# DPT2_4.net
KiCad netlist of a schematic drawn in Altium Designer
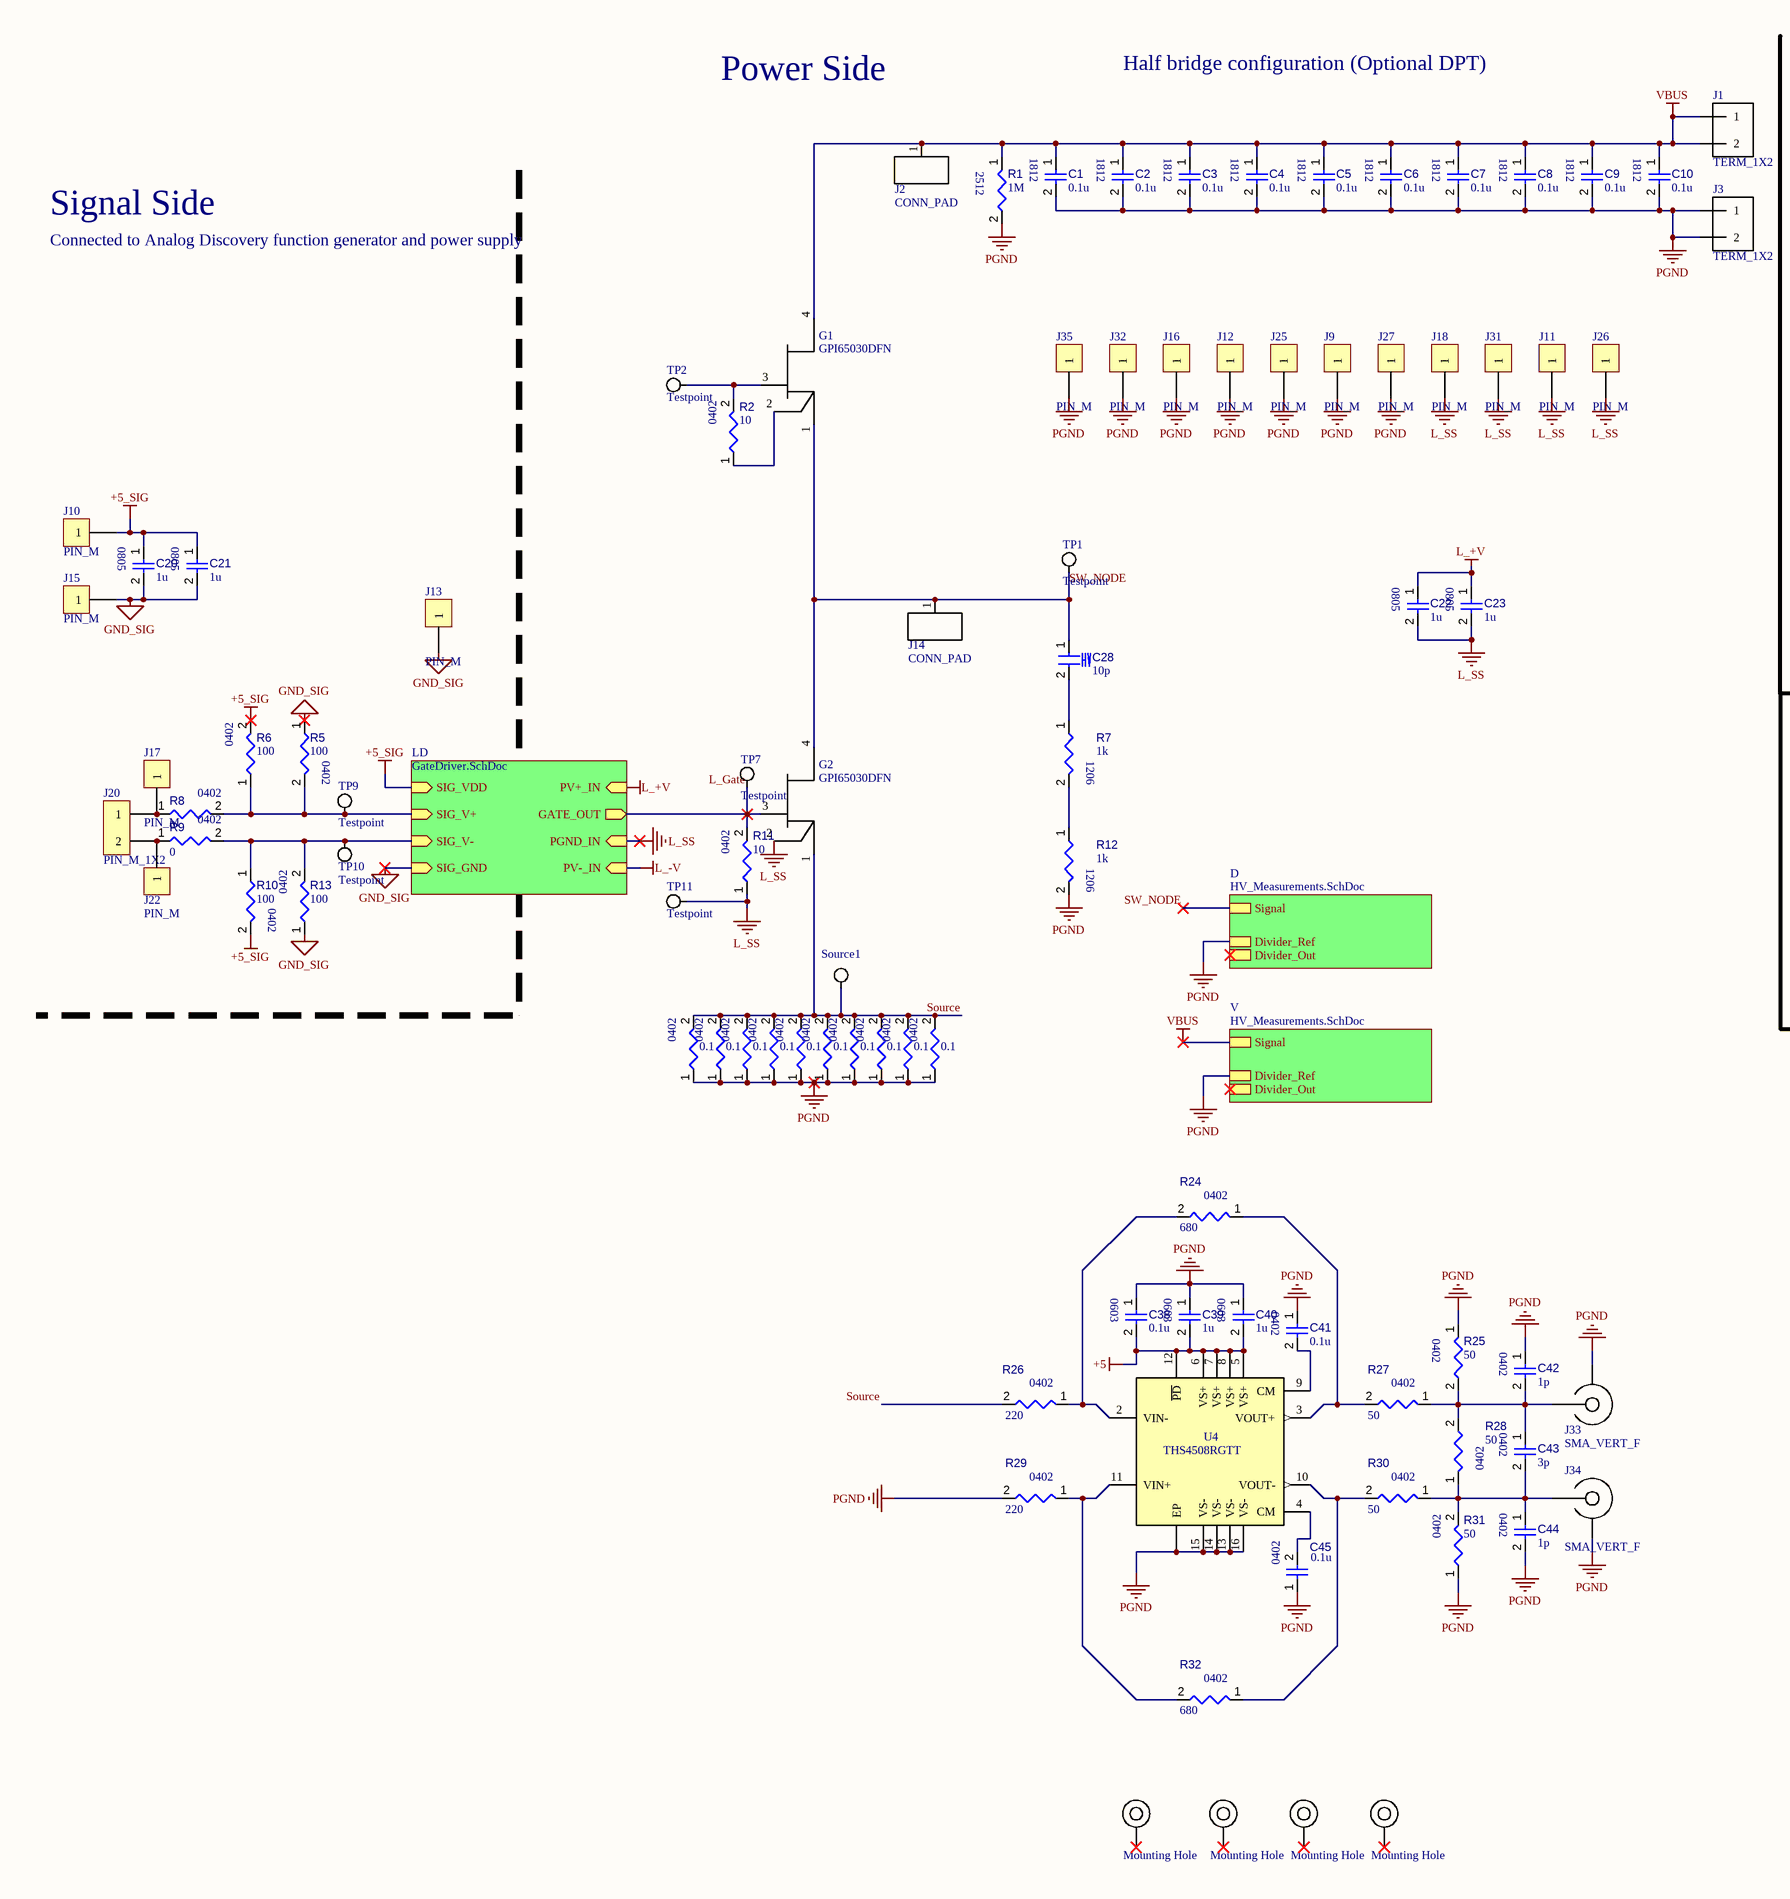
[diagram p0: DPT2.4.SchDoc, left]
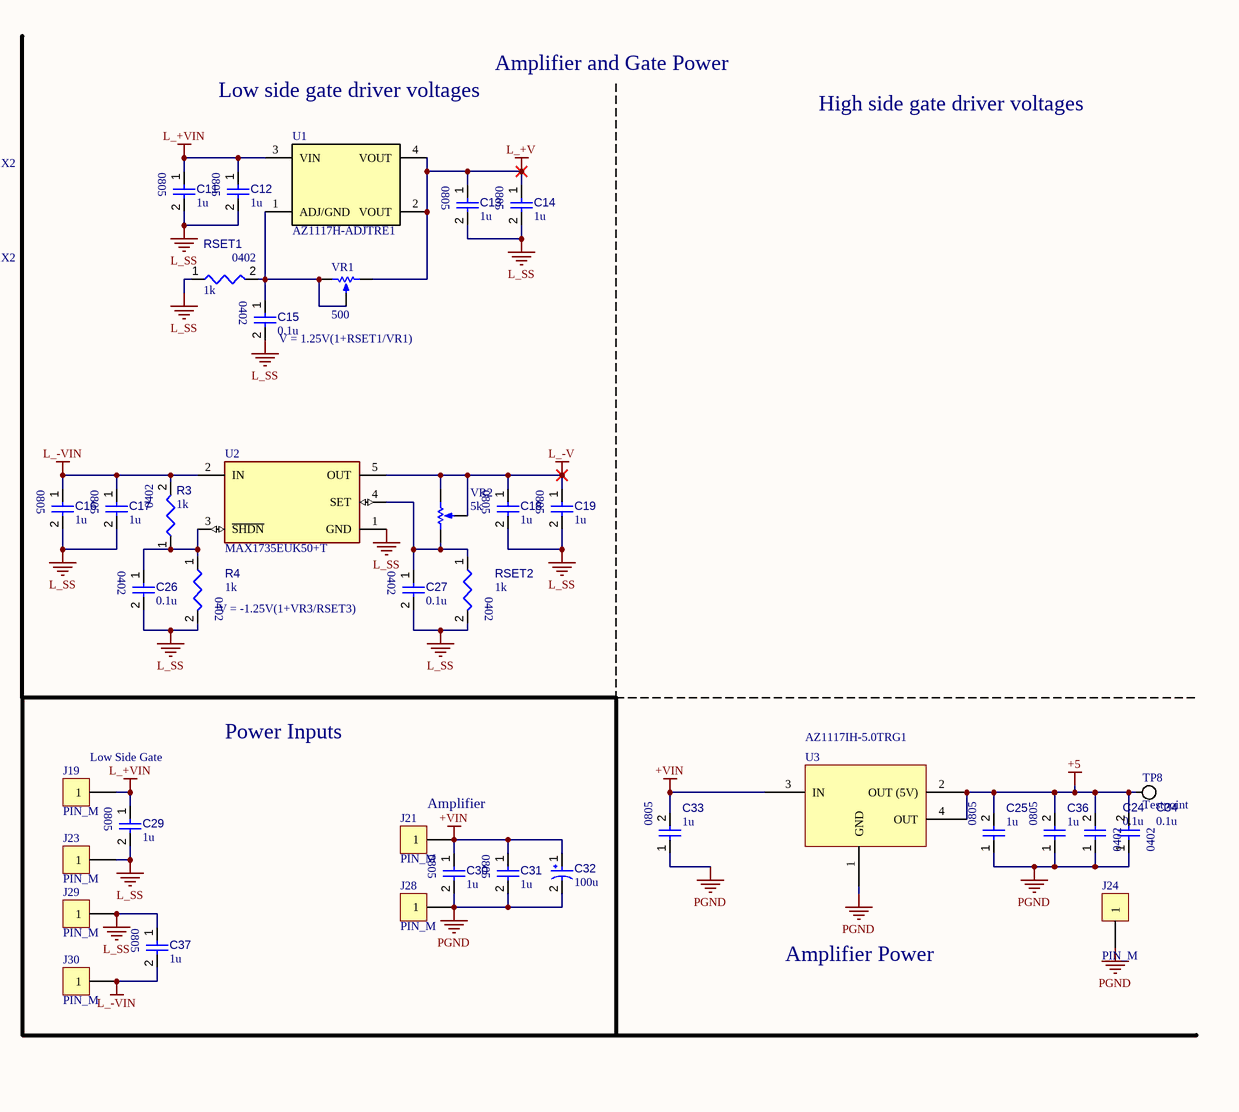
[diagram p1: DPT2.4.SchDoc, right]

(export (version "E")
  (design (tool "Eeschema 10.0.6"))
  (components
    (comp (ref "C1")
      (value "0.1u")
      (footprint "CAP_1812")
      (description "Non polarized SMD capacitor - 1812 (4532 Metric)")
      (fields (field (name "Comment") "CAP-1812"))
      (libsource (lib "2256-GaN Power") (part "CAP-NP-2"))
    )
    (comp (ref "C2")
      (value "0.1u")
      (footprint "CAP_1812")
      (description "Non polarized SMD capacitor - 1812 (4532 Metric)")
      (fields (field (name "Comment") "CAP-1812"))
      (libsource (lib "2256-GaN Power") (part "CAP-NP-2"))
    )
    (comp (ref "C3")
      (value "0.1u")
      (footprint "CAP_1812")
      (description "Non polarized SMD capacitor - 1812 (4532 Metric)")
      (fields (field (name "Comment") "CAP-1812"))
      (libsource (lib "2256-GaN Power") (part "CAP-NP-2"))
    )
    (comp (ref "C4")
      (value "0.1u")
      (footprint "CAP_1812")
      (description "Non polarized SMD capacitor - 1812 (4532 Metric)")
      (fields (field (name "Comment") "CAP-1812"))
      (libsource (lib "2256-GaN Power") (part "CAP-NP-2"))
    )
    (comp (ref "C5")
      (value "0.1u")
      (footprint "CAP_1812")
      (description "Non polarized SMD capacitor - 1812 (4532 Metric)")
      (fields (field (name "Comment") "CAP-1812"))
      (libsource (lib "2256-GaN Power") (part "CAP-NP-2"))
    )
    (comp (ref "C6")
      (value "0.1u")
      (footprint "CAP_1812")
      (description "Non polarized SMD capacitor - 1812 (4532 Metric)")
      (fields (field (name "Comment") "CAP-1812"))
      (libsource (lib "2256-GaN Power") (part "CAP-NP-2"))
    )
    (comp (ref "C7")
      (value "0.1u")
      (footprint "CAP_1812")
      (description "Non polarized SMD capacitor - 1812 (4532 Metric)")
      (fields (field (name "Comment") "CAP-1812"))
      (libsource (lib "2256-GaN Power") (part "CAP-NP-2"))
    )
    (comp (ref "C8")
      (value "0.1u")
      (footprint "CAP_1812")
      (description "Non polarized SMD capacitor - 1812 (4532 Metric)")
      (fields (field (name "Comment") "CAP-1812"))
      (libsource (lib "2256-GaN Power") (part "CAP-NP-2"))
    )
    (comp (ref "C9")
      (value "0.1u")
      (footprint "CAP_1812")
      (description "Non polarized SMD capacitor - 1812 (4532 Metric)")
      (fields (field (name "Comment") "CAP-1812"))
      (libsource (lib "2256-GaN Power") (part "CAP-NP-2"))
    )
    (comp (ref "C10")
      (value "0.1u")
      (footprint "CAP_1812")
      (description "Non polarized SMD capacitor - 1812 (4532 Metric)")
      (fields (field (name "Comment") "CAP-1812"))
      (libsource (lib "2256-GaN Power") (part "CAP-NP-2"))
    )
    (comp (ref "C11")
      (value "1u")
      (footprint "CAP_0805_MED")
      (description "Non polarized SMD capacitor - 0805 (1608 Metric)")
      (fields (field (name "Comment") "CAP-0805"))
      (libsource (lib "2256-GaN Power") (part "CAP-NP-2"))
    )
    (comp (ref "C12")
      (value "1u")
      (footprint "CAP_0805_MED")
      (description "Non polarized SMD capacitor - 0805 (1608 Metric)")
      (fields (field (name "Comment") "CAP-0805"))
      (libsource (lib "2256-GaN Power") (part "CAP-NP-2"))
    )
    (comp (ref "C13")
      (value "1u")
      (footprint "CAP_0805_MED")
      (description "Non polarized SMD capacitor - 0805 (1608 Metric)")
      (fields (field (name "Comment") "CAP-0805"))
      (libsource (lib "2256-GaN Power") (part "CAP-NP-2"))
    )
    (comp (ref "C14")
      (value "1u")
      (footprint "CAP_0805_MED")
      (description "Non polarized SMD capacitor - 0805 (1608 Metric)")
      (fields (field (name "Comment") "CAP-0805"))
      (libsource (lib "2256-GaN Power") (part "CAP-NP-2"))
    )
    (comp (ref "C15")
      (value "0.1u")
      (footprint "CAP_0402_HIGH")
      (description "Non polarized SMD capacitor - 0402 (1005 Metric)")
      (fields (field (name "Comment") "CAP-0402"))
      (libsource (lib "2256-GaN Power") (part "CAP-NP-2"))
    )
    (comp (ref "C16")
      (value "1u")
      (footprint "CAP_0805_MED")
      (description "Non polarized SMD capacitor - 0805 (1608 Metric)")
      (fields (field (name "Comment") "CAP-0805"))
      (libsource (lib "2256-GaN Power") (part "CAP-NP-2"))
    )
    (comp (ref "C17")
      (value "1u")
      (footprint "CAP_0805_MED")
      (description "Non polarized SMD capacitor - 0805 (1608 Metric)")
      (fields (field (name "Comment") "CAP-0805"))
      (libsource (lib "2256-GaN Power") (part "CAP-NP-2"))
    )
    (comp (ref "C18")
      (value "1u")
      (footprint "CAP_0805_MED")
      (description "Non polarized SMD capacitor - 0805 (1608 Metric)")
      (fields (field (name "Comment") "CAP-0805"))
      (libsource (lib "2256-GaN Power") (part "CAP-NP-2"))
    )
    (comp (ref "C19")
      (value "1u")
      (footprint "CAP_0805_MED")
      (description "Non polarized SMD capacitor - 0805 (1608 Metric)")
      (fields (field (name "Comment") "CAP-0805"))
      (libsource (lib "2256-GaN Power") (part "CAP-NP-2"))
    )
    (comp (ref "C20")
      (value "1u")
      (footprint "CAP_0805_MED")
      (description "Non polarized SMD capacitor - 0805 (1608 Metric)")
      (fields (field (name "Comment") "CAP-0805"))
      (libsource (lib "2256-GaN Power") (part "CAP-NP-2"))
    )
    (comp (ref "C21")
      (value "1u")
      (footprint "CAP_0805_MED")
      (description "Non polarized SMD capacitor - 0805 (1608 Metric)")
      (fields (field (name "Comment") "CAP-0805"))
      (libsource (lib "2256-GaN Power") (part "CAP-NP-2"))
    )
    (comp (ref "C22")
      (value "1u")
      (footprint "CAP_0805_MED")
      (description "Non polarized SMD capacitor - 0805 (1608 Metric)")
      (fields (field (name "Comment") "CAP-0805"))
      (libsource (lib "2256-GaN Power") (part "CAP-NP-2"))
    )
    (comp (ref "C23")
      (value "1u")
      (footprint "CAP_0805_MED")
      (description "Non polarized SMD capacitor - 0805 (1608 Metric)")
      (fields (field (name "Comment") "CAP-0805"))
      (libsource (lib "2256-GaN Power") (part "CAP-NP-2"))
    )
    (comp (ref "C24")
      (value "0.1u")
      (footprint "CAP_0402_HIGH")
      (description "Non polarized SMD capacitor - 0402 (1005 Metric)")
      (fields (field (name "Comment") "CAP-0402"))
      (libsource (lib "2256-GaN Power") (part "CAP-NP-2"))
    )
    (comp (ref "C25")
      (value "1u")
      (footprint "CAP_0805_MED")
      (description "Non polarized SMD capacitor - 0805 (1608 Metric)")
      (fields (field (name "Comment") "CAP-0805"))
      (libsource (lib "2256-GaN Power") (part "CAP-NP-2"))
    )
    (comp (ref "C26")
      (value "0.1u")
      (footprint "CAP_0402_HIGH")
      (description "Non polarized SMD capacitor - 0402 (1005 Metric)")
      (fields (field (name "Comment") "CAP-0402"))
      (libsource (lib "2256-GaN Power") (part "CAP-NP-2"))
    )
    (comp (ref "C27")
      (value "0.1u")
      (footprint "CAP_0402_HIGH")
      (description "Non polarized SMD capacitor - 0402 (1005 Metric)")
      (fields (field (name "Comment") "CAP-0402"))
      (libsource (lib "2256-GaN Power") (part "CAP-NP-2"))
    )
    (comp (ref "C28")
      (value "10p")
      (footprint "CAP_1206_HV")
      (description "Non polarized SMD capacitor - 1206 (3216 Metric) High Voltage")
      (fields (field (name "Comment") "CAP-1206-HV"))
      (libsource (lib "2256-GaN Power") (part "CAP-NP-2-HV"))
    )
    (comp (ref "C29")
      (value "1u")
      (footprint "CAP_0805_MED")
      (description "Non polarized SMD capacitor - 0805 (1608 Metric)")
      (fields (field (name "Comment") "CAP-0805"))
      (libsource (lib "2256-GaN Power") (part "CAP-NP-2"))
    )
    (comp (ref "C30")
      (value "1u")
      (footprint "CAP_0805_MED")
      (description "Non polarized SMD capacitor - 0805 (1608 Metric)")
      (fields (field (name "Comment") "CAP-0805"))
      (libsource (lib "2256-GaN Power") (part "CAP-NP-2"))
    )
    (comp (ref "C31")
      (value "1u")
      (footprint "CAP_0805_MED")
      (description "Non polarized SMD capacitor - 0805 (1608 Metric)")
      (fields (field (name "Comment") "CAP-0805"))
      (libsource (lib "2256-GaN Power") (part "CAP-NP-2"))
    )
    (comp (ref "C32")
      (value "100u")
      (footprint "PCAP_2MM_5MM")
      (description "Polarized THT capacitor - Radial can, 2mm lead spacing, 5mm diameter")
      (fields (field (name "Comment") "PCAP-2MMx5MM"))
      (libsource (lib "2256-GaN Power") (part "CAP-P-2"))
    )
    (comp (ref "C33")
      (value "1u")
      (footprint "CAP_0805_MED")
      (description "Non polarized SMD capacitor - 0805 (1608 Metric)")
      (fields (field (name "Comment") "CAP-0805"))
      (libsource (lib "2256-GaN Power") (part "CAP-NP-2"))
    )
    (comp (ref "C34")
      (value "0.1u")
      (footprint "CAP_0402_HIGH")
      (description "Non polarized SMD capacitor - 0402 (1005 Metric)")
      (fields (field (name "Comment") "CAP-0402"))
      (libsource (lib "2256-GaN Power") (part "CAP-NP-2"))
    )
    (comp (ref "C36")
      (value "1u")
      (footprint "CAP_0805_MED")
      (description "Non polarized SMD capacitor - 0805 (1608 Metric)")
      (fields (field (name "Comment") "CAP-0805"))
      (libsource (lib "2256-GaN Power") (part "CAP-NP-2"))
    )
    (comp (ref "C37")
      (value "1u")
      (footprint "CAP_0805_MED")
      (description "Non polarized SMD capacitor - 0805 (1608 Metric)")
      (fields (field (name "Comment") "CAP-0805"))
      (libsource (lib "2256-GaN Power") (part "CAP-NP-2"))
    )
    (comp (ref "C38")
      (value "0.1u")
      (footprint "CAP_0603_HIGH")
      (description "Non polarized SMD capacitor - 0603 (1608 Metric)")
      (fields (field (name "Comment") "CAP-0603"))
      (libsource (lib "2256-GaN Power") (part "CAP-NP-2"))
    )
    (comp (ref "C39")
      (value "1u")
      (footprint "CAP_0603_HIGH")
      (description "Non polarized SMD capacitor - 0603 (1608 Metric)")
      (fields (field (name "Comment") "CAP-0603"))
      (libsource (lib "2256-GaN Power") (part "CAP-NP-2"))
    )
    (comp (ref "C40")
      (value "1u")
      (footprint "CAP_0603_HIGH")
      (description "Non polarized SMD capacitor - 0603 (1608 Metric)")
      (fields (field (name "Comment") "CAP-0603"))
      (libsource (lib "2256-GaN Power") (part "CAP-NP-2"))
    )
    (comp (ref "C41")
      (value "0.1u")
      (footprint "CAP_0402_HIGH")
      (description "Non polarized SMD capacitor - 0402 (1005 Metric)")
      (fields (field (name "Comment") "CAP-0402"))
      (libsource (lib "2256-GaN Power") (part "CAP-NP-2"))
    )
    (comp (ref "C42")
      (value "1p")
      (footprint "CAP_0402_HIGH")
      (description "Non polarized SMD capacitor - 0402 (1005 Metric)")
      (fields (field (name "Comment") "CAP-0402"))
      (libsource (lib "2256-GaN Power") (part "CAP-NP-2"))
    )
    (comp (ref "C43")
      (value "3p")
      (footprint "CAP_0402_HIGH")
      (description "Non polarized SMD capacitor - 0402 (1005 Metric)")
      (fields (field (name "Comment") "CAP-0402"))
      (libsource (lib "2256-GaN Power") (part "CAP-NP-2"))
    )
    (comp (ref "C44")
      (value "1p")
      (footprint "CAP_0402_HIGH")
      (description "Non polarized SMD capacitor - 0402 (1005 Metric)")
      (fields (field (name "Comment") "CAP-0402"))
      (libsource (lib "2256-GaN Power") (part "CAP-NP-2"))
    )
    (comp (ref "C45")
      (value "0.1u")
      (footprint "CAP_0402_HIGH")
      (description "Non polarized SMD capacitor - 0402 (1005 Metric)")
      (fields (field (name "Comment") "CAP-0402"))
      (libsource (lib "2256-GaN Power") (part "CAP-NP-2"))
    )
    (comp (ref "G1")
      (value "GPI65030DFN")
      (footprint "DFN_8X8")
      (description "650V 15A GaN Enhancement mode Transistor")
      (libsource (lib "2256-GaN Power") (part "TRANS_GPI65030DFN"))
    )
    (comp (ref "G2")
      (value "GPI65030DFN")
      (footprint "DFN_8X8")
      (description "650V 15A GaN Enhancement mode Transistor")
      (libsource (lib "2256-GaN Power") (part "TRANS_GPI65030DFN"))
    )
    (comp (ref "J1")
      (value "TERM_1X2")
      (footprint "J_TERM_BLK_1X2")
      (description "Terminal Block 1X2, 6.35mm pitch")
      (libsource (lib "2256-GaN Power") (part "TERM_BLK_1X2"))
    )
    (comp (ref "J2")
      (value "CONN_PAD")
      (footprint "CONN_PAD")
      (description "Solderable Connection Pad")
      (libsource (lib "2256-GaN Power") (part "CONN_PAD"))
    )
    (comp (ref "J3")
      (value "TERM_1X2")
      (footprint "J_TERM_BLK_1X2")
      (description "Terminal Block 1X2, 6.35mm pitch")
      (libsource (lib "2256-GaN Power") (part "TERM_BLK_1X2"))
    )
    (comp (ref "J9")
      (value "PIN_M")
      (footprint "J_THT_1_PIN")
      (description "Male Pin, 1 Pin")
      (libsource (lib "2256-GaN Power") (part "M_PIN_HEAD_1X1"))
    )
    (comp (ref "J10")
      (value "PIN_M")
      (footprint "J_THT_1_PIN")
      (description "Male Pin, 1 Pin")
      (libsource (lib "") (part "M_PIN_HEAD_1X1_1"))
    )
    (comp (ref "J11")
      (value "PIN_M")
      (footprint "J_THT_1_PIN")
      (description "Male Pin, 1 Pin")
      (libsource (lib "2256-GaN Power") (part "M_PIN_HEAD_1X1"))
    )
    (comp (ref "J12")
      (value "PIN_M")
      (footprint "J_THT_1_PIN")
      (description "Male Pin, 1 Pin")
      (libsource (lib "2256-GaN Power") (part "M_PIN_HEAD_1X1"))
    )
    (comp (ref "J13")
      (value "PIN_M")
      (footprint "J_THT_1_PIN")
      (description "Male Pin, 1 Pin")
      (libsource (lib "2256-GaN Power") (part "M_PIN_HEAD_1X1"))
    )
    (comp (ref "J14")
      (value "CONN_PAD")
      (footprint "CONN_PAD")
      (description "Solderable Connection Pad")
      (libsource (lib "2256-GaN Power") (part "CONN_PAD"))
    )
    (comp (ref "J15")
      (value "PIN_M")
      (footprint "J_THT_1_PIN")
      (description "Male Pin, 1 Pin")
      (libsource (lib "") (part "M_PIN_HEAD_1X1_1"))
    )
    (comp (ref "J16")
      (value "PIN_M")
      (footprint "J_THT_1_PIN")
      (description "Male Pin, 1 Pin")
      (libsource (lib "2256-GaN Power") (part "M_PIN_HEAD_1X1"))
    )
    (comp (ref "J17")
      (value "PIN_M")
      (footprint "J_THT_1_PIN")
      (description "Male Pin, 1 Pin")
      (libsource (lib "2256-GaN Power") (part "M_PIN_HEAD_1X1"))
    )
    (comp (ref "J18")
      (value "PIN_M")
      (footprint "J_THT_1_PIN")
      (description "Male Pin, 1 Pin")
      (libsource (lib "2256-GaN Power") (part "M_PIN_HEAD_1X1"))
    )
    (comp (ref "J19")
      (value "PIN_M")
      (footprint "J_THT_1_PIN")
      (description "Male Pin, 1 Pin")
      (libsource (lib "") (part "M_PIN_HEAD_1X1_1"))
    )
    (comp (ref "J20")
      (value "PIN_M_1X2")
      (footprint "J_THT_2.54MM_1X2")
      (description "Male Pin 2.54mm pitch 1X2")
      (libsource (lib "2256-GaN Power") (part "M_PIN_HEAD_1X2"))
    )
    (comp (ref "J21")
      (value "PIN_M")
      (footprint "J_THT_1_PIN")
      (description "Male Pin, 1 Pin")
      (libsource (lib "") (part "M_PIN_HEAD_1X1_1"))
    )
    (comp (ref "J22")
      (value "PIN_M")
      (footprint "J_THT_1_PIN")
      (description "Male Pin, 1 Pin")
      (libsource (lib "") (part "M_PIN_HEAD_1X1_2"))
    )
    (comp (ref "J23")
      (value "PIN_M")
      (footprint "J_THT_1_PIN")
      (description "Male Pin, 1 Pin")
      (libsource (lib "") (part "M_PIN_HEAD_1X1_1"))
    )
    (comp (ref "J24")
      (value "PIN_M")
      (footprint "J_THT_1_PIN")
      (description "Male Pin, 1 Pin")
      (libsource (lib "2256-GaN Power") (part "M_PIN_HEAD_1X1"))
    )
    (comp (ref "J25")
      (value "PIN_M")
      (footprint "J_THT_1_PIN")
      (description "Male Pin, 1 Pin")
      (libsource (lib "2256-GaN Power") (part "M_PIN_HEAD_1X1"))
    )
    (comp (ref "J26")
      (value "PIN_M")
      (footprint "J_THT_1_PIN")
      (description "Male Pin, 1 Pin")
      (libsource (lib "2256-GaN Power") (part "M_PIN_HEAD_1X1"))
    )
    (comp (ref "J27")
      (value "PIN_M")
      (footprint "J_THT_1_PIN")
      (description "Male Pin, 1 Pin")
      (libsource (lib "2256-GaN Power") (part "M_PIN_HEAD_1X1"))
    )
    (comp (ref "J28")
      (value "PIN_M")
      (footprint "J_THT_1_PIN")
      (description "Male Pin, 1 Pin")
      (libsource (lib "") (part "M_PIN_HEAD_1X1_1"))
    )
    (comp (ref "J29")
      (value "PIN_M")
      (footprint "J_THT_1_PIN")
      (description "Male Pin, 1 Pin")
      (libsource (lib "") (part "M_PIN_HEAD_1X1_1"))
    )
    (comp (ref "J30")
      (value "PIN_M")
      (footprint "J_THT_1_PIN")
      (description "Male Pin, 1 Pin")
      (libsource (lib "") (part "M_PIN_HEAD_1X1_1"))
    )
    (comp (ref "J31")
      (value "PIN_M")
      (footprint "J_THT_1_PIN")
      (description "Male Pin, 1 Pin")
      (libsource (lib "2256-GaN Power") (part "M_PIN_HEAD_1X1"))
    )
    (comp (ref "J32")
      (value "PIN_M")
      (footprint "J_THT_1_PIN")
      (description "Male Pin, 1 Pin")
      (libsource (lib "2256-GaN Power") (part "M_PIN_HEAD_1X1"))
    )
    (comp (ref "J33")
      (value "SMA_VERT_F")
      (footprint "SMA_VERT_F")
      (description "SMA connector, Vertical, Female")
      (libsource (lib "2256-GaN Power") (part "SMA_F"))
    )
    (comp (ref "J34")
      (value "SMA_VERT_F")
      (footprint "SMA_VERT_F")
      (description "SMA connector, Vertical, Female")
      (libsource (lib "") (part "SMA_F_1"))
    )
    (comp (ref "J35")
      (value "PIN_M")
      (footprint "J_THT_1_PIN")
      (description "Male Pin, 1 Pin")
      (libsource (lib "2256-GaN Power") (part "M_PIN_HEAD_1X1"))
    )
    (comp (ref "MH1")
      (value "Mounting Hole")
      (footprint "Mounting Hole-Footprint-1")
      (libsource (lib "2256-GaN Power") (part "Mounting Hole-Symbol-1"))
    )
    (comp (ref "MH2")
      (value "Mounting Hole")
      (footprint "Mounting Hole-Footprint-1")
      (libsource (lib "2256-GaN Power") (part "Mounting Hole-Symbol-1"))
    )
    (comp (ref "MH3")
      (value "Mounting Hole")
      (footprint "Mounting Hole-Footprint-1")
      (libsource (lib "2256-GaN Power") (part "Mounting Hole-Symbol-1"))
    )
    (comp (ref "MH4")
      (value "Mounting Hole")
      (footprint "Mounting Hole-Footprint-1")
      (libsource (lib "2256-GaN Power") (part "Mounting Hole-Symbol-1"))
    )
    (comp (ref "R1")
      (value "1M")
      (footprint "RES_2512_MED")
      (description "SMD Resistor - 2512 (6432 Metric)")
      (fields (field (name "Comment") "RES-2512"))
      (libsource (lib "2256-GaN Power") (part "RES-2"))
    )
    (comp (ref "R2")
      (value "10")
      (footprint "RES_0402_HIGH")
      (description "SMD Resistor - 0402 (1005 Metric)")
      (fields (field (name "Comment") "RES-0402"))
      (libsource (lib "2256-GaN Power") (part "RES-2"))
    )
    (comp (ref "R3")
      (value "1k")
      (footprint "RES_0402_HIGH")
      (description "SMD Resistor - 0402 (1005 Metric)")
      (fields (field (name "Comment") "RES-0402"))
      (libsource (lib "2256-GaN Power") (part "RES-2"))
    )
    (comp (ref "R4")
      (value "1k")
      (footprint "RES_0402_HIGH")
      (description "SMD Resistor - 0402 (1005 Metric)")
      (fields (field (name "Comment") "RES-0402"))
      (libsource (lib "2256-GaN Power") (part "RES-2"))
    )
    (comp (ref "R5")
      (value "100")
      (footprint "RES_0402_HIGH")
      (description "SMD Resistor - 0402 (1005 Metric)")
      (fields (field (name "Comment") "RES-0402"))
      (libsource (lib "2256-GaN Power") (part "RES-2"))
    )
    (comp (ref "R6")
      (value "100")
      (footprint "RES_0402_HIGH")
      (description "SMD Resistor - 0402 (1005 Metric)")
      (fields (field (name "Comment") "RES-0402"))
      (libsource (lib "2256-GaN Power") (part "RES-2"))
    )
    (comp (ref "R7")
      (value "1k")
      (footprint "RES_1206_MED")
      (description "SMD Resistor - 1206 (3216 Metric)")
      (fields (field (name "Comment") "RES-1206"))
      (libsource (lib "2256-GaN Power") (part "RES-2"))
    )
    (comp (ref "R8")
      (value "0")
      (footprint "RES_0402_HIGH")
      (description "SMD Resistor - 0402 (1005 Metric)")
      (fields (field (name "Comment") "RES-0402"))
      (libsource (lib "2256-GaN Power") (part "RES-2"))
    )
    (comp (ref "R9")
      (value "0")
      (footprint "RES_0402_HIGH")
      (description "SMD Resistor - 0402 (1005 Metric)")
      (fields (field (name "Comment") "RES-0402"))
      (libsource (lib "2256-GaN Power") (part "RES-2"))
    )
    (comp (ref "R10")
      (value "100")
      (footprint "RES_0402_HIGH")
      (description "SMD Resistor - 0402 (1005 Metric)")
      (fields (field (name "Comment") "RES-0402"))
      (libsource (lib "2256-GaN Power") (part "RES-2"))
    )
    (comp (ref "R11")
      (value "10")
      (footprint "RES_0402_HIGH")
      (description "SMD Resistor - 0402 (1005 Metric)")
      (fields (field (name "Comment") "RES-0402"))
      (libsource (lib "2256-GaN Power") (part "RES-2"))
    )
    (comp (ref "R12")
      (value "1k")
      (footprint "RES_1206_MED")
      (description "SMD Resistor - 1206 (3216 Metric)")
      (fields (field (name "Comment") "RES-1206"))
      (libsource (lib "2256-GaN Power") (part "RES-2"))
    )
    (comp (ref "R13")
      (value "100")
      (footprint "RES_0402_HIGH")
      (description "SMD Resistor - 0402 (1005 Metric)")
      (fields (field (name "Comment") "RES-0402"))
      (libsource (lib "2256-GaN Power") (part "RES-2"))
    )
    (comp (ref "R14")
      (value "0.1")
      (footprint "RES_0402_HIGH")
      (description "SMD Resistor - 0402 (1005 Metric)")
      (fields (field (name "Comment") "RES-0402"))
      (libsource (lib "2256-GaN Power") (part "RES-2"))
    )
    (comp (ref "R15")
      (value "0.1")
      (footprint "RES_0402_HIGH")
      (description "SMD Resistor - 0402 (1005 Metric)")
      (fields (field (name "Comment") "RES-0402"))
      (libsource (lib "2256-GaN Power") (part "RES-2"))
    )
    (comp (ref "R16")
      (value "0.1")
      (footprint "RES_0402_HIGH")
      (description "SMD Resistor - 0402 (1005 Metric)")
      (fields (field (name "Comment") "RES-0402"))
      (libsource (lib "2256-GaN Power") (part "RES-2"))
    )
    (comp (ref "R17")
      (value "0.1")
      (footprint "RES_0402_HIGH")
      (description "SMD Resistor - 0402 (1005 Metric)")
      (fields (field (name "Comment") "RES-0402"))
      (libsource (lib "2256-GaN Power") (part "RES-2"))
    )
    (comp (ref "R18")
      (value "0.1")
      (footprint "RES_0402_HIGH")
      (description "SMD Resistor - 0402 (1005 Metric)")
      (fields (field (name "Comment") "RES-0402"))
      (libsource (lib "2256-GaN Power") (part "RES-2"))
    )
    (comp (ref "R19")
      (value "0.1")
      (footprint "RES_0402_HIGH")
      (description "SMD Resistor - 0402 (1005 Metric)")
      (fields (field (name "Comment") "RES-0402"))
      (libsource (lib "2256-GaN Power") (part "RES-2"))
    )
    (comp (ref "R20")
      (value "0.1")
      (footprint "RES_0402_HIGH")
      (description "SMD Resistor - 0402 (1005 Metric)")
      (fields (field (name "Comment") "RES-0402"))
      (libsource (lib "2256-GaN Power") (part "RES-2"))
    )
    (comp (ref "R21")
      (value "0.1")
      (footprint "RES_0402_HIGH")
      (description "SMD Resistor - 0402 (1005 Metric)")
      (fields (field (name "Comment") "RES-0402"))
      (libsource (lib "2256-GaN Power") (part "RES-2"))
    )
    (comp (ref "R22")
      (value "0.1")
      (footprint "RES_0402_HIGH")
      (description "SMD Resistor - 0402 (1005 Metric)")
      (fields (field (name "Comment") "RES-0402"))
      (libsource (lib "2256-GaN Power") (part "RES-2"))
    )
    (comp (ref "R23")
      (value "0.1")
      (footprint "RES_0402_HIGH")
      (description "SMD Resistor - 0402 (1005 Metric)")
      (fields (field (name "Comment") "RES-0402"))
      (libsource (lib "2256-GaN Power") (part "RES-2"))
    )
    (comp (ref "R24")
      (value "680")
      (footprint "RES_0402_HIGH")
      (description "SMD Resistor - 0402 (1005 Metric)")
      (fields (field (name "Comment") "RES-0402"))
      (libsource (lib "2256-GaN Power") (part "RES-2"))
    )
    (comp (ref "R25")
      (value "50")
      (footprint "RES_0402_HIGH")
      (description "SMD Resistor - 0402 (1005 Metric)")
      (fields (field (name "Comment") "RES-0402"))
      (libsource (lib "2256-GaN Power") (part "RES-2"))
    )
    (comp (ref "R26")
      (value "220")
      (footprint "RES_0402_HIGH")
      (description "SMD Resistor - 0402 (1005 Metric)")
      (fields (field (name "Comment") "RES-0402"))
      (libsource (lib "2256-GaN Power") (part "RES-2"))
    )
    (comp (ref "R27")
      (value "50")
      (footprint "RES_0402_HIGH")
      (description "SMD Resistor - 0402 (1005 Metric)")
      (fields (field (name "Comment") "RES-0402"))
      (libsource (lib "2256-GaN Power") (part "RES-2"))
    )
    (comp (ref "R28")
      (value "50")
      (footprint "RES_0402_HIGH")
      (description "SMD Resistor - 0402 (1005 Metric)")
      (fields (field (name "Comment") "RES-0402"))
      (libsource (lib "2256-GaN Power") (part "RES-2"))
    )
    (comp (ref "R29")
      (value "220")
      (footprint "RES_0402_HIGH")
      (description "SMD Resistor - 0402 (1005 Metric)")
      (fields (field (name "Comment") "RES-0402"))
      (libsource (lib "2256-GaN Power") (part "RES-2"))
    )
    (comp (ref "R30")
      (value "50")
      (footprint "RES_0402_HIGH")
      (description "SMD Resistor - 0402 (1005 Metric)")
      (fields (field (name "Comment") "RES-0402"))
      (libsource (lib "2256-GaN Power") (part "RES-2"))
    )
    (comp (ref "R31")
      (value "50")
      (footprint "RES_0402_HIGH")
      (description "SMD Resistor - 0402 (1005 Metric)")
      (fields (field (name "Comment") "RES-0402"))
      (libsource (lib "2256-GaN Power") (part "RES-2"))
    )
    (comp (ref "R32")
      (value "680")
      (footprint "RES_0402_HIGH")
      (description "SMD Resistor - 0402 (1005 Metric)")
      (fields (field (name "Comment") "RES-0402"))
      (libsource (lib "2256-GaN Power") (part "RES-2"))
    )
    (comp (ref "RSET1")
      (value "1k")
      (footprint "RES_0402_HIGH")
      (description "SMD Resistor - 0402 (1005 Metric)")
      (fields (field (name "Comment") "RES-0402"))
      (libsource (lib "2256-GaN Power") (part "RES-2"))
    )
    (comp (ref "RSET2")
      (value "1k")
      (footprint "RES_0402_HIGH")
      (description "SMD Resistor - 0402 (1005 Metric)")
      (fields (field (name "Comment") "RES-0402"))
      (libsource (lib "2256-GaN Power") (part "RES-2"))
    )
    (comp (ref "Source1")
      (value "Testpoint")
      (footprint "Testpoint-Footprint-1")
      (description "testpoint for circuit")
      (libsource (lib "2256-GaN Power") (part "Testpoint-Symbol-1"))
    )
    (comp (ref "TP1")
      (value "Testpoint")
      (footprint "Testpoint-Footprint-1")
      (description "testpoint for circuit")
      (libsource (lib "2256-GaN Power") (part "Testpoint-Symbol-1"))
    )
    (comp (ref "TP2")
      (value "Testpoint")
      (footprint "Testpoint-Footprint-1")
      (description "testpoint for circuit")
      (libsource (lib "2256-GaN Power") (part "Testpoint-Symbol-1"))
    )
    (comp (ref "TP7")
      (value "Testpoint")
      (footprint "Testpoint-Footprint-1")
      (description "testpoint for circuit")
      (libsource (lib "2256-GaN Power") (part "Testpoint-Symbol-1"))
    )
    (comp (ref "TP8")
      (value "Testpoint")
      (footprint "Testpoint-Footprint-1")
      (description "testpoint for circuit")
      (libsource (lib "2256-GaN Power") (part "Testpoint-Symbol-1"))
    )
    (comp (ref "TP9")
      (value "Testpoint")
      (footprint "Testpoint-Footprint-1")
      (description "testpoint for circuit")
      (libsource (lib "2256-GaN Power") (part "Testpoint-Symbol-1"))
    )
    (comp (ref "TP10")
      (value "Testpoint")
      (footprint "Testpoint-Footprint-1")
      (description "testpoint for circuit")
      (libsource (lib "2256-GaN Power") (part "Testpoint-Symbol-1"))
    )
    (comp (ref "TP11")
      (value "Testpoint")
      (footprint "Testpoint-Footprint-1")
      (description "testpoint for circuit")
      (libsource (lib "2256-GaN Power") (part "Testpoint-Symbol-1"))
    )
    (comp (ref "U1")
      (value "AZ1117H-ADJTRE1")
      (footprint "SOT-223")
      (description "IC REG LINEAR POS ADJ 1A SOT223")
      (libsource (lib "2256-GaN Power") (part "AZ1117H-ADJTRE1"))
    )
    (comp (ref "U2")
      (value "MAX1735EUK50+T")
      (footprint "FP-U5-2-IPC_B")
      (description "IC REG LIN NEG ADJ 200MA SOT23-5")
      (libsource (lib "Altium Content Vault") (part "3fe5ddc4f403acdf696fd8e1856eecf"))
    )
    (comp (ref "U3")
      (value "AZ1117IH-5.0TRG1")
      (footprint "SOT230P700X180-4N")
      (description "https://www.digikey.ca/en/products/detail/diodes-incorporated/AZ1117IH-5-0TRG1/5699673")
      (libsource (lib "2256-GaN Power") (part "AZ1117IH-5.0TRG1-Symbol-1"))
    )
    (comp (ref "U4")
      (value "THS4508RGTT")
      (footprint "QFN-16")
      (description "WIDEBAND, LOW NOISE, LOW DISTORTION FULLY DIFFERENTIAL AMPLIFIER")
      (libsource (lib "2256-GaN Power") (part "THS4508"))
    )
    (comp (ref "VR1")
      (value "500")
      (footprint "TRIM_J-LEAD")
      (description "Potentiometer, J-Lead Trim Pot")
      (fields (field (name "Comment") "RES_POT_JLEAD"))
      (libsource (lib "2256-GaN Power") (part "RES-POT-3"))
    )
    (comp (ref "VR2")
      (value "5k")
      (footprint "TRIM_J-LEAD")
      (description "Potentiometer, J-Lead Trim Pot")
      (fields (field (name "Comment") "RES_POT_JLEAD"))
      (libsource (lib "2256-GaN Power") (part "RES-POT-3"))
    )
  )
  (nets
    (net (code "1") (name "+5") (class "Default")
      (node (ref "C24") (pin "2") (pinfunction "2_2") (pintype "passive"))
      (node (ref "C25") (pin "2") (pinfunction "2_2") (pintype "passive"))
      (node (ref "C34") (pin "2") (pinfunction "2_2") (pintype "passive"))
      (node (ref "C36") (pin "2") (pinfunction "2_2") (pintype "passive"))
      (node (ref "C38") (pin "2") (pinfunction "2_2") (pintype "passive"))
      (node (ref "C39") (pin "2") (pinfunction "2_2") (pintype "passive"))
      (node (ref "C40") (pin "2") (pinfunction "2_2") (pintype "passive"))
      (node (ref "TP8") (pin "1") (pinfunction "1_1") (pintype "passive"))
      (node (ref "U3") (pin "2") (pinfunction "OUT_(5V)_2") (pintype "passive"))
      (node (ref "U3") (pin "4") (pinfunction "OUT_4") (pintype "passive"))
      (node (ref "U4") (pin "12") (pinfunction "~{PD}_12") (pintype "passive"))
      (node (ref "U4") (pin "5") (pinfunction "VS+_5") (pintype "power_in"))
      (node (ref "U4") (pin "6") (pinfunction "VS+_6") (pintype "power_in"))
      (node (ref "U4") (pin "7") (pinfunction "VS+_7") (pintype "power_in"))
      (node (ref "U4") (pin "8") (pinfunction "VS+_8") (pintype "power_in"))
    )
    (net (code "2") (name "+5_SIG") (class "Default")
      (node (ref "C20") (pin "1") (pinfunction "1_1") (pintype "passive"))
      (node (ref "C21") (pin "1") (pinfunction "1_1") (pintype "passive"))
      (node (ref "J10") (pin "1") (pinfunction "1_1") (pintype "passive"))
      (node (ref "R10") (pin "2") (pinfunction "2_2") (pintype "passive"))
      (node (ref "R6") (pin "2") (pinfunction "2_2") (pintype "passive"))
    )
    (net (code "3") (name "+VIN") (class "Default")
      (node (ref "C30") (pin "1") (pinfunction "1_1") (pintype "passive"))
      (node (ref "C31") (pin "1") (pinfunction "1_1") (pintype "passive"))
      (node (ref "C32") (pin "1") (pinfunction "1_1") (pintype "passive"))
      (node (ref "C33") (pin "2") (pinfunction "2_2") (pintype "passive"))
      (node (ref "J21") (pin "1") (pinfunction "1_1") (pintype "passive"))
      (node (ref "U3") (pin "3") (pinfunction "IN_3") (pintype "passive"))
    )
    (net (code "6") (name "/L_Gate") (class "Default")
      (node (ref "G2") (pin "3") (pinfunction "G_3") (pintype "passive"))
      (node (ref "R11") (pin "2") (pinfunction "2_2") (pintype "passive"))
      (node (ref "TP7") (pin "1") (pinfunction "1_1") (pintype "passive"))
    )
    (net (code "7") (name "/SIG_V+") (class "Default")
      (node (ref "R5") (pin "2") (pinfunction "2_2") (pintype "passive"))
      (node (ref "R6") (pin "1") (pinfunction "1_1") (pintype "passive"))
      (node (ref "R8") (pin "2") (pinfunction "2_2") (pintype "passive"))
      (node (ref "TP9") (pin "1") (pinfunction "1_1") (pintype "passive"))
    )
    (net (code "8") (name "/SIG_V-") (class "Default")
      (node (ref "R10") (pin "1") (pinfunction "1_1") (pintype "passive"))
      (node (ref "R13") (pin "2") (pinfunction "2_2") (pintype "passive"))
      (node (ref "R9") (pin "2") (pinfunction "2_2") (pintype "passive"))
      (node (ref "TP10") (pin "1") (pinfunction "1_1") (pintype "passive"))
    )
    (net (code "9") (name "/SW_NODE") (class "Default")
      (node (ref "C28") (pin "1") (pinfunction "1_1") (pintype "passive"))
      (node (ref "G1") (pin "1") (pinfunction "S_1") (pintype "passive"))
      (node (ref "G2") (pin "4") (pinfunction "D_4") (pintype "passive"))
      (node (ref "J14") (pin "1") (pinfunction "1_1") (pintype "passive"))
      (node (ref "TP1") (pin "1") (pinfunction "1_1") (pintype "passive"))
    )
    (net (code "10") (name "/Source") (class "Default")
      (node (ref "G2") (pin "1") (pinfunction "S_1") (pintype "passive"))
      (node (ref "R14") (pin "2") (pinfunction "2_2") (pintype "passive"))
      (node (ref "R15") (pin "2") (pinfunction "2_2") (pintype "passive"))
      (node (ref "R16") (pin "2") (pinfunction "2_2") (pintype "passive"))
      (node (ref "R17") (pin "2") (pinfunction "2_2") (pintype "passive"))
      (node (ref "R18") (pin "2") (pinfunction "2_2") (pintype "passive"))
      (node (ref "R19") (pin "2") (pinfunction "2_2") (pintype "passive"))
      (node (ref "R20") (pin "2") (pinfunction "2_2") (pintype "passive"))
      (node (ref "R21") (pin "2") (pinfunction "2_2") (pintype "passive"))
      (node (ref "R22") (pin "2") (pinfunction "2_2") (pintype "passive"))
      (node (ref "R23") (pin "2") (pinfunction "2_2") (pintype "passive"))
      (node (ref "R26") (pin "2") (pinfunction "2_2") (pintype "passive"))
      (node (ref "Source1") (pin "1") (pinfunction "1_1") (pintype "passive"))
    )
    (net (code "11") (name "GND_SIG") (class "Default")
      (node (ref "C20") (pin "2") (pinfunction "2_2") (pintype "passive"))
      (node (ref "C21") (pin "2") (pinfunction "2_2") (pintype "passive"))
      (node (ref "J13") (pin "1") (pinfunction "1_1") (pintype "passive"))
      (node (ref "J15") (pin "1") (pinfunction "1_1") (pintype "passive"))
      (node (ref "R13") (pin "1") (pinfunction "1_1") (pintype "passive"))
      (node (ref "R5") (pin "1") (pinfunction "1_1") (pintype "passive"))
    )
    (net (code "12") (name "L_+V") (class "Default")
      (node (ref "C13") (pin "1") (pinfunction "1_1") (pintype "passive"))
      (node (ref "C14") (pin "1") (pinfunction "1_1") (pintype "passive"))
      (node (ref "C22") (pin "1") (pinfunction "1_1") (pintype "passive"))
      (node (ref "C23") (pin "1") (pinfunction "1_1") (pintype "passive"))
      (node (ref "U1") (pin "2") (pinfunction "VOUT_2") (pintype "passive"))
      (node (ref "U1") (pin "4") (pinfunction "VOUT_4") (pintype "passive"))
      (node (ref "VR1") (pin "1") (pinfunction "CCW_1") (pintype "passive"))
    )
    (net (code "13") (name "L_+VIN") (class "Default")
      (node (ref "C11") (pin "1") (pinfunction "1_1") (pintype "passive"))
      (node (ref "C12") (pin "1") (pinfunction "1_1") (pintype "passive"))
      (node (ref "C29") (pin "1") (pinfunction "1_1") (pintype "passive"))
      (node (ref "J19") (pin "1") (pinfunction "1_1") (pintype "passive"))
      (node (ref "U1") (pin "3") (pinfunction "VIN_3") (pintype "passive"))
    )
    (net (code "14") (name "L_-V") (class "Default")
      (node (ref "C18") (pin "1") (pinfunction "1_1") (pintype "passive"))
      (node (ref "C19") (pin "1") (pinfunction "1_1") (pintype "passive"))
      (node (ref "U2") (pin "5") (pinfunction "OUT_5") (pintype "passive"))
      (node (ref "VR2") (pin "2") (pinfunction "S_2") (pintype "passive"))
      (node (ref "VR2") (pin "3") (pinfunction "CW_3") (pintype "passive"))
    )
    (net (code "15") (name "L_-VIN") (class "Default")
      (node (ref "C16") (pin "1") (pinfunction "1_1") (pintype "passive"))
      (node (ref "C17") (pin "1") (pinfunction "1_1") (pintype "passive"))
      (node (ref "C37") (pin "2") (pinfunction "2_2") (pintype "passive"))
      (node (ref "J30") (pin "1") (pinfunction "1_1") (pintype "passive"))
      (node (ref "R3") (pin "2") (pinfunction "2_2") (pintype "passive"))
      (node (ref "U2") (pin "2") (pinfunction "IN_2") (pintype "power_in"))
    )
    (net (code "16") (name "L_SS") (class "Default")
      (node (ref "C11") (pin "2") (pinfunction "2_2") (pintype "passive"))
      (node (ref "C12") (pin "2") (pinfunction "2_2") (pintype "passive"))
      (node (ref "C13") (pin "2") (pinfunction "2_2") (pintype "passive"))
      (node (ref "C14") (pin "2") (pinfunction "2_2") (pintype "passive"))
      (node (ref "C15") (pin "2") (pinfunction "2_2") (pintype "passive"))
      (node (ref "C16") (pin "2") (pinfunction "2_2") (pintype "passive"))
      (node (ref "C17") (pin "2") (pinfunction "2_2") (pintype "passive"))
      (node (ref "C18") (pin "2") (pinfunction "2_2") (pintype "passive"))
      (node (ref "C19") (pin "2") (pinfunction "2_2") (pintype "passive"))
      (node (ref "C22") (pin "2") (pinfunction "2_2") (pintype "passive"))
      (node (ref "C23") (pin "2") (pinfunction "2_2") (pintype "passive"))
      (node (ref "C26") (pin "2") (pinfunction "2_2") (pintype "passive"))
      (node (ref "C27") (pin "2") (pinfunction "2_2") (pintype "passive"))
      (node (ref "C29") (pin "2") (pinfunction "2_2") (pintype "passive"))
      (node (ref "C37") (pin "1") (pinfunction "1_1") (pintype "passive"))
      (node (ref "G2") (pin "2") (pinfunction "KS_2") (pintype "passive"))
      (node (ref "J11") (pin "1") (pinfunction "1_1") (pintype "passive"))
      (node (ref "J18") (pin "1") (pinfunction "1_1") (pintype "passive"))
      (node (ref "J23") (pin "1") (pinfunction "1_1") (pintype "passive"))
      (node (ref "J26") (pin "1") (pinfunction "1_1") (pintype "passive"))
      (node (ref "J29") (pin "1") (pinfunction "1_1") (pintype "passive"))
      (node (ref "J31") (pin "1") (pinfunction "1_1") (pintype "passive"))
      (node (ref "R11") (pin "1") (pinfunction "1_1") (pintype "passive"))
      (node (ref "R4") (pin "2") (pinfunction "2_2") (pintype "passive"))
      (node (ref "RSET1") (pin "1") (pinfunction "1_1") (pintype "passive"))
      (node (ref "RSET2") (pin "2") (pinfunction "2_2") (pintype "passive"))
      (node (ref "TP11") (pin "1") (pinfunction "1_1") (pintype "passive"))
      (node (ref "U2") (pin "1") (pinfunction "GND_1") (pintype "power_in"))
    )
    (net (code "17") (name "Net-(C28-Pad2)") (class "Default")
      (node (ref "C28") (pin "2") (pinfunction "2_2") (pintype "passive"))
      (node (ref "R7") (pin "1") (pinfunction "1_1") (pintype "passive"))
    )
    (net (code "18") (name "Net-(C41-Pad2)") (class "Default")
      (node (ref "C41") (pin "2") (pinfunction "2_2") (pintype "passive"))
      (node (ref "U4") (pin "9") (pinfunction "CM_9") (pintype "passive"))
    )
    (net (code "19") (name "Net-(C42-Pad2)") (class "Default")
      (node (ref "C42") (pin "2") (pinfunction "2_2") (pintype "passive"))
      (node (ref "C43") (pin "1") (pinfunction "1_1") (pintype "passive"))
      (node (ref "J33") (pin "1") (pinfunction "1_1") (pintype "passive"))
      (node (ref "R25") (pin "2") (pinfunction "2_2") (pintype "passive"))
      (node (ref "R27") (pin "1") (pinfunction "1_1") (pintype "passive"))
      (node (ref "R28") (pin "2") (pinfunction "2_2") (pintype "passive"))
    )
    (net (code "20") (name "Net-(C43-Pad2)") (class "Default")
      (node (ref "C43") (pin "2") (pinfunction "2_2") (pintype "passive"))
      (node (ref "C44") (pin "1") (pinfunction "1_1") (pintype "passive"))
      (node (ref "J34") (pin "1") (pinfunction "1_1") (pintype "passive"))
      (node (ref "R28") (pin "1") (pinfunction "1_1") (pintype "passive"))
      (node (ref "R30") (pin "1") (pinfunction "1_1") (pintype "passive"))
      (node (ref "R31") (pin "2") (pinfunction "2_2") (pintype "passive"))
    )
    (net (code "21") (name "Net-(C45-Pad2)") (class "Default")
      (node (ref "C45") (pin "2") (pinfunction "2_2") (pintype "passive"))
      (node (ref "U4") (pin "4") (pinfunction "CM_4") (pintype "passive"))
    )
    (net (code "22") (name "Net-(G1-G)") (class "Default")
      (node (ref "G1") (pin "3") (pinfunction "G_3") (pintype "passive"))
      (node (ref "R2") (pin "2") (pinfunction "2_2") (pintype "passive"))
      (node (ref "TP2") (pin "1") (pinfunction "1_1") (pintype "passive"))
    )
    (net (code "23") (name "Net-(G1-KS)") (class "Default")
      (node (ref "G1") (pin "2") (pinfunction "KS_2") (pintype "passive"))
      (node (ref "R2") (pin "1") (pinfunction "1_1") (pintype "passive"))
    )
    (net (code "24") (name "Net-(J17-Pad1)") (class "Default")
      (node (ref "J17") (pin "1") (pinfunction "1_1") (pintype "passive"))
      (node (ref "J20") (pin "1") (pinfunction "1_1") (pintype "passive"))
      (node (ref "R8") (pin "1") (pinfunction "1_1") (pintype "passive"))
    )
    (net (code "25") (name "Net-(J20-Pad2)") (class "Default")
      (node (ref "J20") (pin "2") (pinfunction "2_2") (pintype "passive"))
      (node (ref "J22") (pin "1") (pinfunction "1_1") (pintype "passive"))
      (node (ref "R9") (pin "1") (pinfunction "1_1") (pintype "passive"))
    )
    (net (code "26") (name "Net-(R12-Pad1)") (class "Default")
      (node (ref "R12") (pin "1") (pinfunction "1_1") (pintype "passive"))
      (node (ref "R7") (pin "2") (pinfunction "2_2") (pintype "passive"))
    )
    (net (code "27") (name "Net-(U1-ADJ{slash}GND)") (class "Default")
      (node (ref "C15") (pin "1") (pinfunction "1_1") (pintype "passive"))
      (node (ref "RSET1") (pin "2") (pinfunction "2_2") (pintype "passive"))
      (node (ref "U1") (pin "1") (pinfunction "ADJ/GND_1") (pintype "passive"))
      (node (ref "VR1") (pin "2") (pinfunction "S_2") (pintype "passive"))
      (node (ref "VR1") (pin "3") (pinfunction "CW_3") (pintype "passive"))
    )
    (net (code "28") (name "Net-(U2-SET)") (class "Default")
      (node (ref "C27") (pin "1") (pinfunction "1_1") (pintype "passive"))
      (node (ref "RSET2") (pin "1") (pinfunction "1_1") (pintype "passive"))
      (node (ref "U2") (pin "4") (pinfunction "SET_4") (pintype "bidirectional"))
      (node (ref "VR2") (pin "1") (pinfunction "CCW_1") (pintype "passive"))
    )
    (net (code "29") (name "Net-(U2-~{SHDN})") (class "Default")
      (node (ref "C26") (pin "1") (pinfunction "1_1") (pintype "passive"))
      (node (ref "R3") (pin "1") (pinfunction "1_1") (pintype "passive"))
      (node (ref "R4") (pin "1") (pinfunction "1_1") (pintype "passive"))
      (node (ref "U2") (pin "3") (pinfunction "~{SHDN}_3") (pintype "bidirectional"))
    )
    (net (code "30") (name "Net-(U4-VIN+)") (class "Default")
      (node (ref "R29") (pin "1") (pinfunction "1_1") (pintype "passive"))
      (node (ref "R32") (pin "2") (pinfunction "2_2") (pintype "passive"))
      (node (ref "U4") (pin "11") (pinfunction "VIN+_11") (pintype "passive"))
    )
    (net (code "31") (name "Net-(U4-VIN-)") (class "Default")
      (node (ref "R24") (pin "2") (pinfunction "2_2") (pintype "passive"))
      (node (ref "R26") (pin "1") (pinfunction "1_1") (pintype "passive"))
      (node (ref "U4") (pin "2") (pinfunction "VIN-_2") (pintype "passive"))
    )
    (net (code "32") (name "Net-(U4-VOUT+)") (class "Default")
      (node (ref "R24") (pin "1") (pinfunction "1_1") (pintype "passive"))
      (node (ref "R27") (pin "2") (pinfunction "2_2") (pintype "passive"))
      (node (ref "U4") (pin "3") (pinfunction "VOUT+_3") (pintype "output"))
    )
    (net (code "33") (name "Net-(U4-VOUT-)") (class "Default")
      (node (ref "R30") (pin "2") (pinfunction "2_2") (pintype "passive"))
      (node (ref "R32") (pin "1") (pinfunction "1_1") (pintype "passive"))
      (node (ref "U4") (pin "10") (pinfunction "VOUT-_10") (pintype "output"))
    )
    (net (code "34") (name "PGND") (class "Default")
      (node (ref "C1") (pin "2") (pinfunction "2_2") (pintype "passive"))
      (node (ref "C10") (pin "2") (pinfunction "2_2") (pintype "passive"))
      (node (ref "C2") (pin "2") (pinfunction "2_2") (pintype "passive"))
      (node (ref "C24") (pin "1") (pinfunction "1_1") (pintype "passive"))
      (node (ref "C25") (pin "1") (pinfunction "1_1") (pintype "passive"))
      (node (ref "C3") (pin "2") (pinfunction "2_2") (pintype "passive"))
      (node (ref "C30") (pin "2") (pinfunction "2_2") (pintype "passive"))
      (node (ref "C31") (pin "2") (pinfunction "2_2") (pintype "passive"))
      (node (ref "C32") (pin "2") (pinfunction "2_2") (pintype "passive"))
      (node (ref "C33") (pin "1") (pinfunction "1_1") (pintype "passive"))
      (node (ref "C34") (pin "1") (pinfunction "1_1") (pintype "passive"))
      (node (ref "C36") (pin "1") (pinfunction "1_1") (pintype "passive"))
      (node (ref "C38") (pin "1") (pinfunction "1_1") (pintype "passive"))
      (node (ref "C39") (pin "1") (pinfunction "1_1") (pintype "passive"))
      (node (ref "C4") (pin "2") (pinfunction "2_2") (pintype "passive"))
      (node (ref "C40") (pin "1") (pinfunction "1_1") (pintype "passive"))
      (node (ref "C41") (pin "1") (pinfunction "1_1") (pintype "passive"))
      (node (ref "C42") (pin "1") (pinfunction "1_1") (pintype "passive"))
      (node (ref "C44") (pin "2") (pinfunction "2_2") (pintype "passive"))
      (node (ref "C45") (pin "1") (pinfunction "1_1") (pintype "passive"))
      (node (ref "C5") (pin "2") (pinfunction "2_2") (pintype "passive"))
      (node (ref "C6") (pin "2") (pinfunction "2_2") (pintype "passive"))
      (node (ref "C7") (pin "2") (pinfunction "2_2") (pintype "passive"))
      (node (ref "C8") (pin "2") (pinfunction "2_2") (pintype "passive"))
      (node (ref "C9") (pin "2") (pinfunction "2_2") (pintype "passive"))
      (node (ref "J12") (pin "1") (pinfunction "1_1") (pintype "passive"))
      (node (ref "J16") (pin "1") (pinfunction "1_1") (pintype "passive"))
      (node (ref "J24") (pin "1") (pinfunction "1_1") (pintype "passive"))
      (node (ref "J25") (pin "1") (pinfunction "1_1") (pintype "passive"))
      (node (ref "J27") (pin "1") (pinfunction "1_1") (pintype "passive"))
      (node (ref "J28") (pin "1") (pinfunction "1_1") (pintype "passive"))
      (node (ref "J3") (pin "1") (pinfunction "1_1") (pintype "passive"))
      (node (ref "J3") (pin "2") (pinfunction "2_2") (pintype "passive"))
      (node (ref "J32") (pin "1") (pinfunction "1_1") (pintype "passive"))
      (node (ref "J33") (pin "2") (pinfunction "2_2") (pintype "passive"))
      (node (ref "J34") (pin "2") (pinfunction "2_2") (pintype "passive"))
      (node (ref "J35") (pin "1") (pinfunction "1_1") (pintype "passive"))
      (node (ref "J9") (pin "1") (pinfunction "1_1") (pintype "passive"))
      (node (ref "R1") (pin "2") (pinfunction "2_2") (pintype "passive"))
      (node (ref "R12") (pin "2") (pinfunction "2_2") (pintype "passive"))
      (node (ref "R14") (pin "1") (pinfunction "1_1") (pintype "passive"))
      (node (ref "R15") (pin "1") (pinfunction "1_1") (pintype "passive"))
      (node (ref "R16") (pin "1") (pinfunction "1_1") (pintype "passive"))
      (node (ref "R17") (pin "1") (pinfunction "1_1") (pintype "passive"))
      (node (ref "R18") (pin "1") (pinfunction "1_1") (pintype "passive"))
      (node (ref "R19") (pin "1") (pinfunction "1_1") (pintype "passive"))
      (node (ref "R20") (pin "1") (pinfunction "1_1") (pintype "passive"))
      (node (ref "R21") (pin "1") (pinfunction "1_1") (pintype "passive"))
      (node (ref "R22") (pin "1") (pinfunction "1_1") (pintype "passive"))
      (node (ref "R23") (pin "1") (pinfunction "1_1") (pintype "passive"))
      (node (ref "R25") (pin "1") (pinfunction "1_1") (pintype "passive"))
      (node (ref "R29") (pin "2") (pinfunction "2_2") (pintype "passive"))
      (node (ref "R31") (pin "1") (pinfunction "1_1") (pintype "passive"))
      (node (ref "U3") (pin "1") (pinfunction "GND_1") (pintype "passive"))
      (node (ref "U4") (pin "13") (pinfunction "VS-_13") (pintype "power_in"))
      (node (ref "U4") (pin "14") (pinfunction "VS-_14") (pintype "power_in"))
      (node (ref "U4") (pin "15") (pinfunction "VS-_15") (pintype "power_in"))
      (node (ref "U4") (pin "16") (pinfunction "VS-_16") (pintype "power_in"))
      (node (ref "U4") (pin "17") (pinfunction "EP_17") (pintype "power_in"))
    )
    (net (code "35") (name "VBUS") (class "Default")
      (node (ref "C1") (pin "1") (pinfunction "1_1") (pintype "passive"))
      (node (ref "C10") (pin "1") (pinfunction "1_1") (pintype "passive"))
      (node (ref "C2") (pin "1") (pinfunction "1_1") (pintype "passive"))
      (node (ref "C3") (pin "1") (pinfunction "1_1") (pintype "passive"))
      (node (ref "C4") (pin "1") (pinfunction "1_1") (pintype "passive"))
      (node (ref "C5") (pin "1") (pinfunction "1_1") (pintype "passive"))
      (node (ref "C6") (pin "1") (pinfunction "1_1") (pintype "passive"))
      (node (ref "C7") (pin "1") (pinfunction "1_1") (pintype "passive"))
      (node (ref "C8") (pin "1") (pinfunction "1_1") (pintype "passive"))
      (node (ref "C9") (pin "1") (pinfunction "1_1") (pintype "passive"))
      (node (ref "G1") (pin "4") (pinfunction "D_4") (pintype "passive"))
      (node (ref "J1") (pin "1") (pinfunction "1_1") (pintype "passive"))
      (node (ref "J1") (pin "2") (pinfunction "2_2") (pintype "passive"))
      (node (ref "J2") (pin "1") (pinfunction "1_1") (pintype "passive"))
      (node (ref "R1") (pin "1") (pinfunction "1_1") (pintype "passive"))
    )
    (net (code "36") (name "unconnected-(MH1-GND-Pad1)") (class "Default")
      (node (ref "MH1") (pin "1") (pinfunction "GND_1") (pintype "passive+no_connect"))
    )
    (net (code "37") (name "unconnected-(MH2-GND-Pad1)") (class "Default")
      (node (ref "MH2") (pin "1") (pinfunction "GND_1") (pintype "passive+no_connect"))
    )
    (net (code "38") (name "unconnected-(MH3-GND-Pad1)") (class "Default")
      (node (ref "MH3") (pin "1") (pinfunction "GND_1") (pintype "passive+no_connect"))
    )
    (net (code "39") (name "unconnected-(MH4-GND-Pad1)") (class "Default")
      (node (ref "MH4") (pin "1") (pinfunction "GND_1") (pintype "passive+no_connect"))
    )
  )
)
